# SCH_MedySync_2024-07-15.net
KiCad netlist of a schematic drawn in EasyEDA
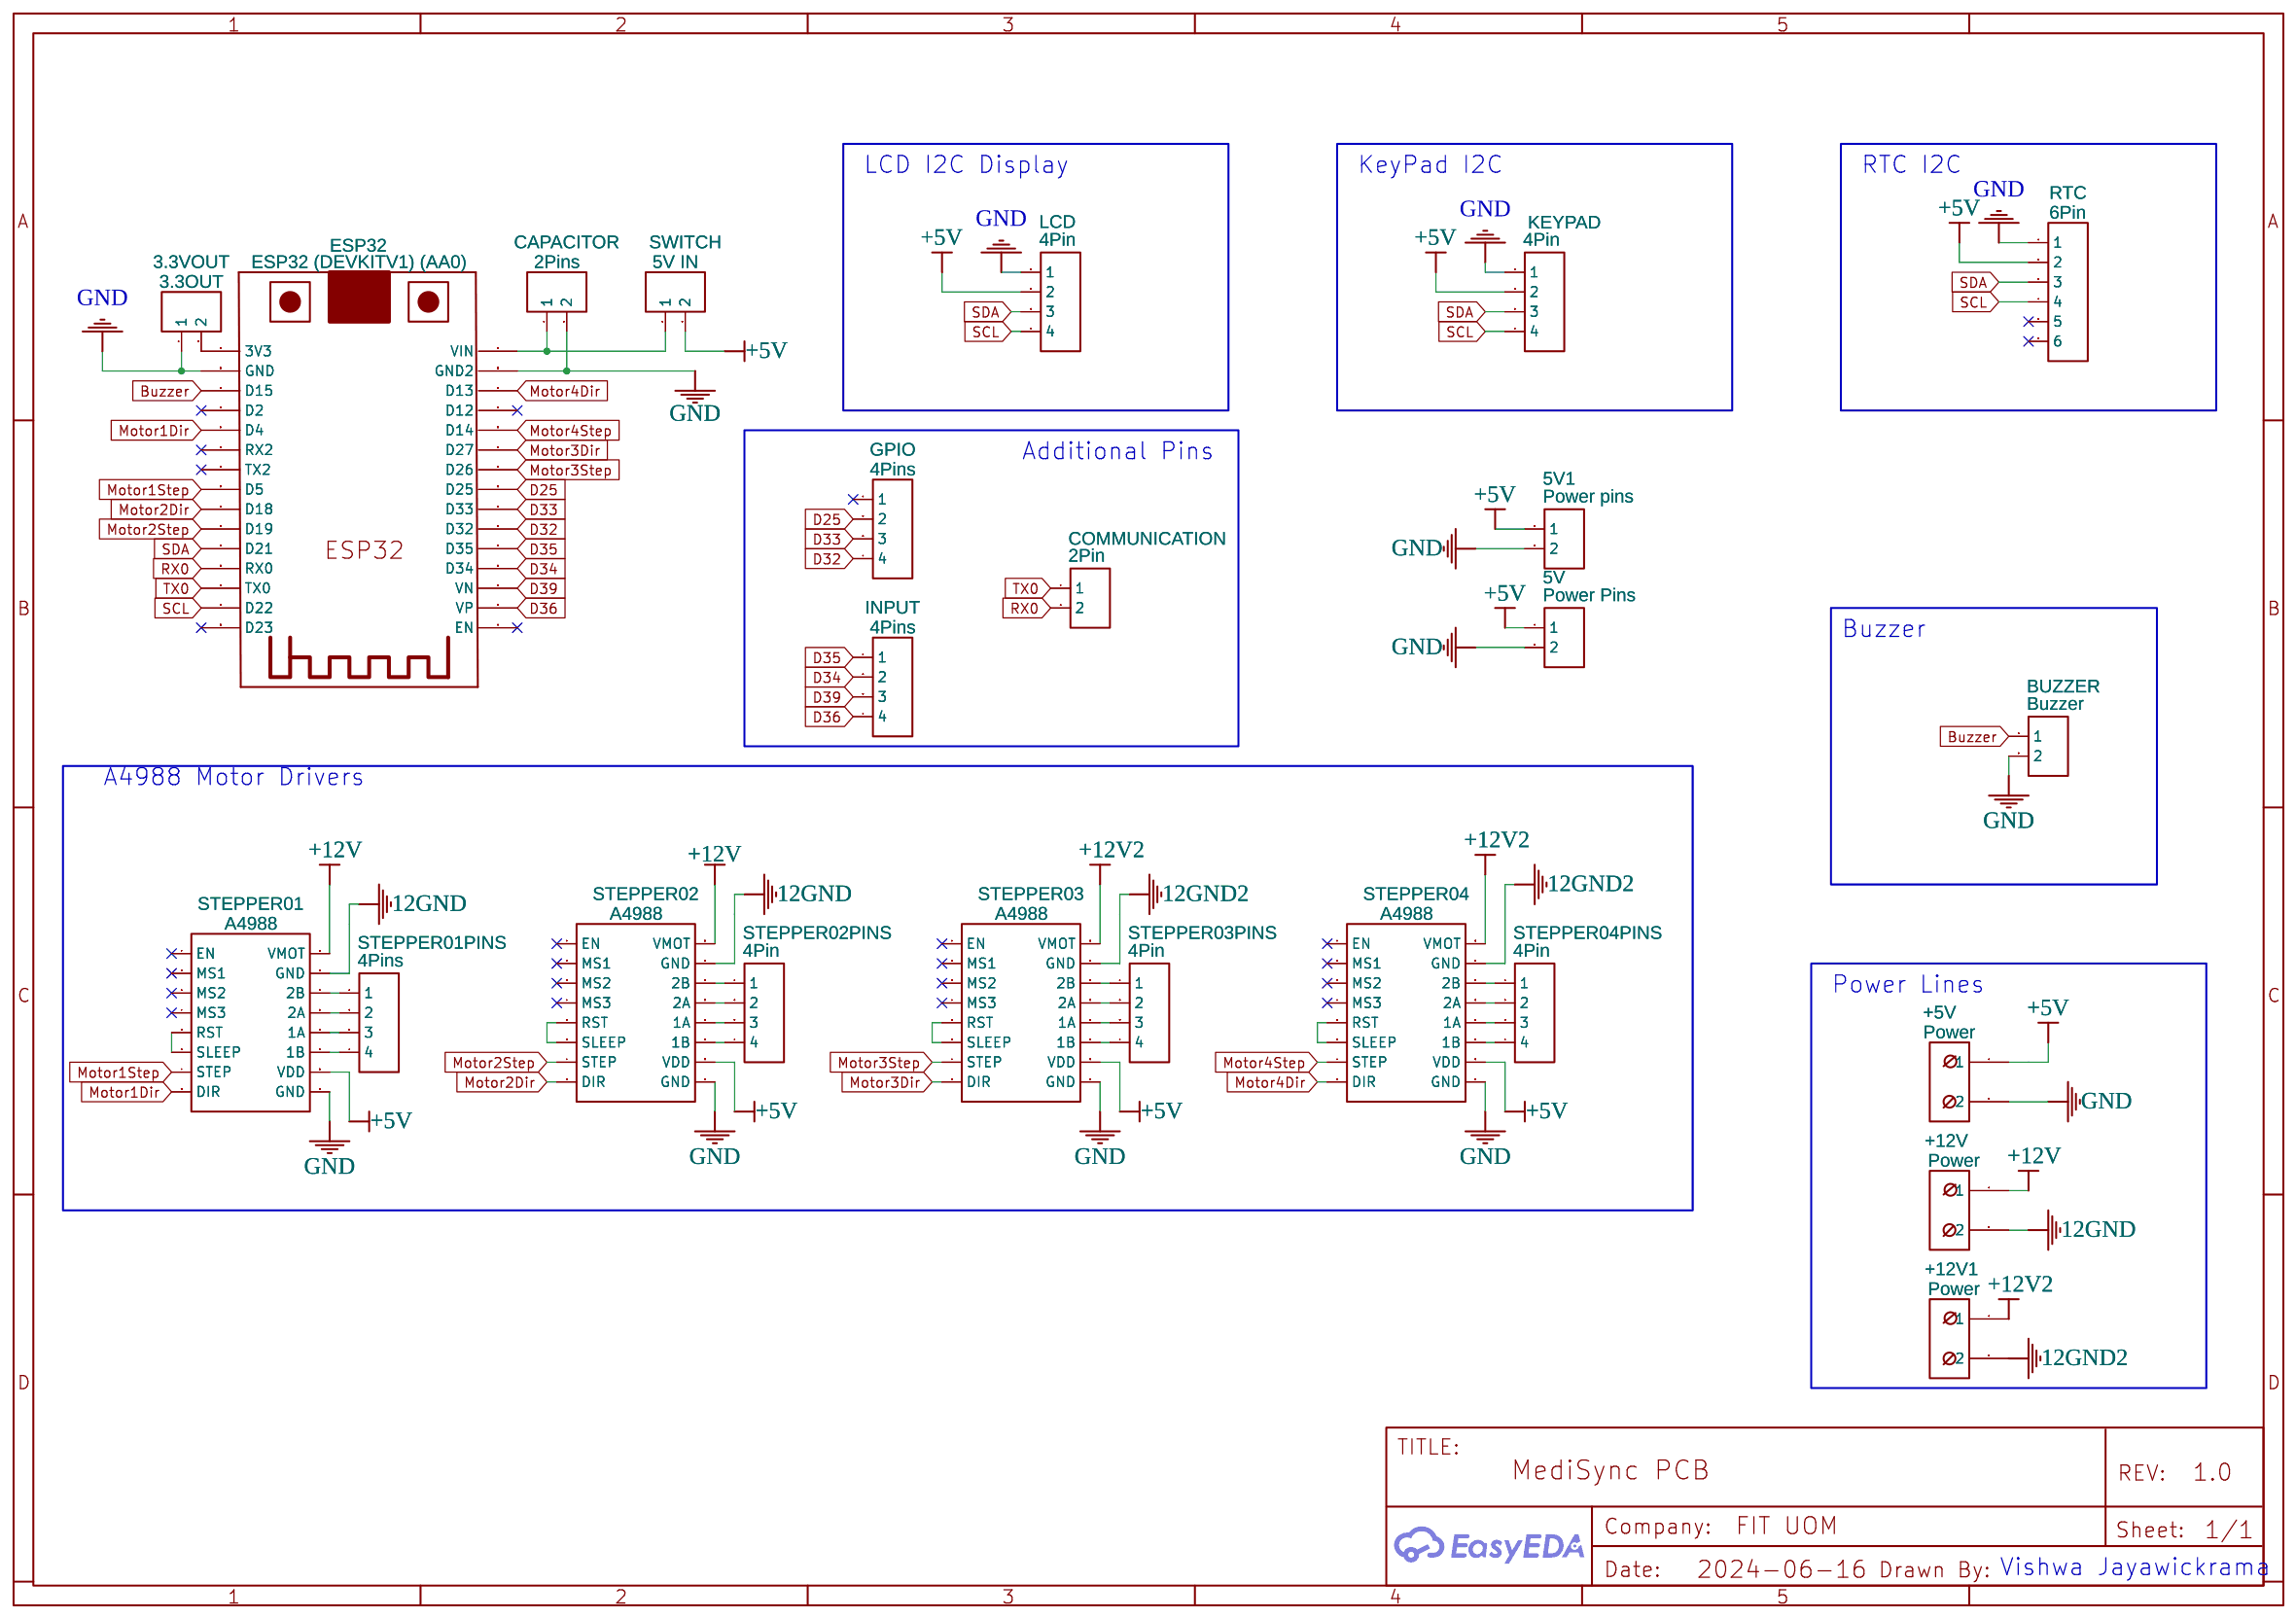
[diagram p0: schematic sheet]

(export (version "E")
  (design (tool "Eeschema 10.0.6"))
  (components
    (comp (ref "+5V") (value "Power") (libsource (lib "") (part "2POSITION_TERMINAL_BLOCK_1")))
    (comp (ref "+12V") (value "Power") (libsource (lib "") (part "2POSITION_TERMINAL_BLOCK")))
    (comp (ref "+12V1") (value "Power") (libsource (lib "") (part "2POSITION_TERMINAL_BLOCK")))
    (comp (ref "3.3VOUT") (value "3.3OUT") (libsource (lib "") (part "HDR-M-2.54_1x2_3")))
    (comp (ref "5V") (value "Power Pins") (libsource (lib "") (part "HDR-M-2.54_1x2")))
    (comp (ref "5V1") (value "Power pins") (libsource (lib "") (part "HDR-M-2.54_1x2")))
    (comp (ref "BUZZER") (value "Buzzer") (libsource (lib "") (part "HDR-M-2.54_1x2_2")))
    (comp (ref "CAPACITOR") (value "2Pins") (libsource (lib "") (part "HDR-F-2.54_1x2")))
    (comp (ref "COMMUNICATION") (value "2Pin") (libsource (lib "") (part "HDR-M-2.54_1x2_1")))
    (comp (ref "ESP32") (value "ESP32 (DEVKITV1) (AA0)") (libsource (lib "") (part "ESP32-DEVKIT-V1-30PIN")))
    (comp (ref "GPIO") (value "4Pins") (libsource (lib "") (part "HDR-M-2.54_1x4_3")))
    (comp (ref "INPUT") (value "4Pins") (libsource (lib "") (part "HDR-M-2.54_1x4_2")))
    (comp (ref "KEYPAD") (value "4Pin") (libsource (lib "") (part "HDR-M-2.54_1x4_6")))
    (comp (ref "LCD") (value "4Pin") (libsource (lib "") (part "HDR-M-2.54_1x4_7")))
    (comp (ref "RTC") (value "6Pin") (libsource (lib "") (part "HDR-F-2.54_1x6")))
    (comp (ref "STEPPER01") (value "A4988") (libsource (lib "") (part "A4988")))
    (comp (ref "STEPPER01PINS") (value "4Pins") (libsource (lib "") (part "HDR-M-2.54_1x4_4")))
    (comp (ref "STEPPER02") (value "A4988") (libsource (lib "") (part "A4988")))
    (comp (ref "STEPPER02PINS") (value "4Pin") (libsource (lib "") (part "HDR-M-2.54_1x4")))
    (comp (ref "STEPPER03") (value "A4988") (libsource (lib "") (part "A4988")))
    (comp (ref "STEPPER03PINS") (value "4Pin") (libsource (lib "") (part "HDR-M-2.54_1x4_1")))
    (comp (ref "STEPPER04") (value "A4988") (libsource (lib "") (part "A4988")))
    (comp (ref "STEPPER04PINS") (value "4Pin") (libsource (lib "") (part "HDR-M-2.54_1x4_5")))
    (comp (ref "SWITCH") (value "5V IN") (libsource (lib "") (part "HDR-M-2.54_1x2_4")))
  )
  (nets
    (net (code "1") (name "+5V") (class "Default")
      (node (ref "+5V") (pin "1") (pinfunction "1_1") (pintype "unspecified"))
      (node (ref "5V") (pin "1") (pinfunction "1_1") (pintype "unspecified"))
      (node (ref "5V1") (pin "1") (pinfunction "1_1") (pintype "unspecified"))
      (node (ref "KEYPAD") (pin "2") (pinfunction "2_2") (pintype "unspecified"))
      (node (ref "LCD") (pin "2") (pinfunction "2_2") (pintype "unspecified"))
      (node (ref "RTC") (pin "2") (pinfunction "2_2") (pintype "input"))
      (node (ref "STEPPER01") (pin "15") (pinfunction "VDD_15") (pintype "unspecified"))
      (node (ref "STEPPER02") (pin "15") (pinfunction "VDD_15") (pintype "unspecified"))
      (node (ref "STEPPER03") (pin "15") (pinfunction "VDD_15") (pintype "unspecified"))
      (node (ref "STEPPER04") (pin "15") (pinfunction "VDD_15") (pintype "unspecified"))
      (node (ref "SWITCH") (pin "2") (pinfunction "2_2") (pintype "unspecified"))
    )
    (net (code "2") (name "+12V") (class "Default")
      (node (ref "+12V") (pin "1") (pinfunction "1_1") (pintype "unspecified"))
      (node (ref "STEPPER01") (pin "9") (pinfunction "VMOT_9") (pintype "unspecified"))
      (node (ref "STEPPER02") (pin "9") (pinfunction "VMOT_9") (pintype "unspecified"))
    )
    (net (code "3") (name "+12V2") (class "Default")
      (node (ref "+12V1") (pin "1") (pinfunction "1_1") (pintype "unspecified"))
      (node (ref "STEPPER03") (pin "9") (pinfunction "VMOT_9") (pintype "unspecified"))
      (node (ref "STEPPER04") (pin "9") (pinfunction "VMOT_9") (pintype "unspecified"))
    )
    (net (code "4") (name "12GND") (class "Default")
      (node (ref "+12V") (pin "2") (pinfunction "2_2") (pintype "unspecified"))
      (node (ref "STEPPER01") (pin "10") (pinfunction "GND_10") (pintype "unspecified"))
      (node (ref "STEPPER02") (pin "10") (pinfunction "GND_10") (pintype "unspecified"))
    )
    (net (code "5") (name "12GND2") (class "Default")
      (node (ref "+12V1") (pin "2") (pinfunction "2_2") (pintype "unspecified"))
      (node (ref "STEPPER03") (pin "10") (pinfunction "GND_10") (pintype "unspecified"))
      (node (ref "STEPPER04") (pin "10") (pinfunction "GND_10") (pintype "unspecified"))
    )
    (net (code "6") (name "Buzzer") (class "Default")
      (node (ref "BUZZER") (pin "1") (pinfunction "1_1") (pintype "unspecified"))
      (node (ref "ESP32") (pin "D15") (pinfunction "D15_D15") (pintype "unspecified"))
    )
    (net (code "7") (name "D25") (class "Default")
      (node (ref "ESP32") (pin "D25") (pinfunction "D25_D25") (pintype "unspecified"))
      (node (ref "GPIO") (pin "2") (pinfunction "2_2") (pintype "unspecified"))
    )
    (net (code "8") (name "D32") (class "Default")
      (node (ref "ESP32") (pin "D32") (pinfunction "D32_D32") (pintype "unspecified"))
      (node (ref "GPIO") (pin "4") (pinfunction "4_4") (pintype "unspecified"))
    )
    (net (code "9") (name "D33") (class "Default")
      (node (ref "ESP32") (pin "D33") (pinfunction "D33_D33") (pintype "unspecified"))
      (node (ref "GPIO") (pin "3") (pinfunction "3_3") (pintype "unspecified"))
    )
    (net (code "10") (name "D34") (class "Default")
      (node (ref "ESP32") (pin "D34") (pinfunction "D34_D34") (pintype "unspecified"))
      (node (ref "INPUT") (pin "2") (pinfunction "2_2") (pintype "unspecified"))
    )
    (net (code "11") (name "D35") (class "Default")
      (node (ref "ESP32") (pin "D35") (pinfunction "D35_D35") (pintype "unspecified"))
      (node (ref "INPUT") (pin "1") (pinfunction "1_1") (pintype "unspecified"))
    )
    (net (code "12") (name "D36") (class "Default")
      (node (ref "ESP32") (pin "VP") (pinfunction "VP_VP") (pintype "unspecified"))
      (node (ref "INPUT") (pin "4") (pinfunction "4_4") (pintype "unspecified"))
    )
    (net (code "13") (name "D39") (class "Default")
      (node (ref "ESP32") (pin "VN") (pinfunction "VN_VN") (pintype "unspecified"))
      (node (ref "INPUT") (pin "3") (pinfunction "3_3") (pintype "unspecified"))
    )
    (net (code "14") (name "GND") (class "Default")
      (node (ref "+5V") (pin "2") (pinfunction "2_2") (pintype "unspecified"))
      (node (ref "3.3VOUT") (pin "1") (pinfunction "1_1") (pintype "unspecified"))
      (node (ref "5V") (pin "2") (pinfunction "2_2") (pintype "unspecified"))
      (node (ref "5V1") (pin "2") (pinfunction "2_2") (pintype "unspecified"))
      (node (ref "BUZZER") (pin "2") (pinfunction "2_2") (pintype "unspecified"))
      (node (ref "CAPACITOR") (pin "2") (pinfunction "2_2") (pintype "input"))
      (node (ref "ESP32") (pin "GND") (pinfunction "GND_GND") (pintype "unspecified"))
      (node (ref "ESP32") (pin "GND2") (pinfunction "GND2_GND2") (pintype "unspecified"))
      (node (ref "KEYPAD") (pin "1") (pinfunction "1_1") (pintype "unspecified"))
      (node (ref "LCD") (pin "1") (pinfunction "1_1") (pintype "unspecified"))
      (node (ref "RTC") (pin "1") (pinfunction "1_1") (pintype "input"))
      (node (ref "STEPPER01") (pin "16") (pinfunction "GND_16") (pintype "unspecified"))
      (node (ref "STEPPER02") (pin "16") (pinfunction "GND_16") (pintype "unspecified"))
      (node (ref "STEPPER03") (pin "16") (pinfunction "GND_16") (pintype "unspecified"))
      (node (ref "STEPPER04") (pin "16") (pinfunction "GND_16") (pintype "unspecified"))
    )
    (net (code "15") (name "Motor1Dir") (class "Default")
      (node (ref "ESP32") (pin "D4") (pinfunction "D4_D4") (pintype "unspecified"))
      (node (ref "STEPPER01") (pin "8") (pinfunction "DIR_8") (pintype "unspecified"))
    )
    (net (code "16") (name "Motor1Step") (class "Default")
      (node (ref "ESP32") (pin "D5") (pinfunction "D5_D5") (pintype "unspecified"))
      (node (ref "STEPPER01") (pin "7") (pinfunction "STEP_7") (pintype "unspecified"))
    )
    (net (code "17") (name "Motor2Dir") (class "Default")
      (node (ref "ESP32") (pin "D18") (pinfunction "D18_D18") (pintype "unspecified"))
      (node (ref "STEPPER02") (pin "8") (pinfunction "DIR_8") (pintype "unspecified"))
    )
    (net (code "18") (name "Motor2Step") (class "Default")
      (node (ref "ESP32") (pin "D19") (pinfunction "D19_D19") (pintype "unspecified"))
      (node (ref "STEPPER02") (pin "7") (pinfunction "STEP_7") (pintype "unspecified"))
    )
    (net (code "19") (name "Motor3Dir") (class "Default")
      (node (ref "ESP32") (pin "D27") (pinfunction "D27_D27") (pintype "unspecified"))
      (node (ref "STEPPER03") (pin "8") (pinfunction "DIR_8") (pintype "unspecified"))
    )
    (net (code "20") (name "Motor3Step") (class "Default")
      (node (ref "ESP32") (pin "D26") (pinfunction "D26_D26") (pintype "unspecified"))
      (node (ref "STEPPER03") (pin "7") (pinfunction "STEP_7") (pintype "unspecified"))
    )
    (net (code "21") (name "Motor4Dir") (class "Default")
      (node (ref "ESP32") (pin "D13") (pinfunction "D13_D13") (pintype "unspecified"))
      (node (ref "STEPPER04") (pin "8") (pinfunction "DIR_8") (pintype "unspecified"))
    )
    (net (code "22") (name "Motor4Step") (class "Default")
      (node (ref "ESP32") (pin "D14") (pinfunction "D14_D14") (pintype "unspecified"))
      (node (ref "STEPPER04") (pin "7") (pinfunction "STEP_7") (pintype "unspecified"))
    )
    (net (code "23") (name "Net-(3.3VOUT-Pad2)") (class "Default")
      (node (ref "3.3VOUT") (pin "2") (pinfunction "2_2") (pintype "unspecified"))
      (node (ref "ESP32") (pin "3V3") (pinfunction "3V3_3V3") (pintype "unspecified"))
    )
    (net (code "24") (name "Net-(CAPACITOR-Pad1)") (class "Default")
      (node (ref "CAPACITOR") (pin "1") (pinfunction "1_1") (pintype "input"))
      (node (ref "ESP32") (pin "VIN") (pinfunction "VIN_VIN") (pintype "unspecified"))
      (node (ref "SWITCH") (pin "1") (pinfunction "1_1") (pintype "unspecified"))
    )
    (net (code "25") (name "Net-(STEPPER01-1A)") (class "Default")
      (node (ref "STEPPER01") (pin "13") (pinfunction "1A_13") (pintype "unspecified"))
      (node (ref "STEPPER01PINS") (pin "3") (pinfunction "3_3") (pintype "unspecified"))
    )
    (net (code "26") (name "Net-(STEPPER01-1B)") (class "Default")
      (node (ref "STEPPER01") (pin "14") (pinfunction "1B_14") (pintype "unspecified"))
      (node (ref "STEPPER01PINS") (pin "4") (pinfunction "4_4") (pintype "unspecified"))
    )
    (net (code "27") (name "Net-(STEPPER01-2A)") (class "Default")
      (node (ref "STEPPER01") (pin "12") (pinfunction "2A_12") (pintype "unspecified"))
      (node (ref "STEPPER01PINS") (pin "2") (pinfunction "2_2") (pintype "unspecified"))
    )
    (net (code "28") (name "Net-(STEPPER01-2B)") (class "Default")
      (node (ref "STEPPER01") (pin "11") (pinfunction "2B_11") (pintype "unspecified"))
      (node (ref "STEPPER01PINS") (pin "1") (pinfunction "1_1") (pintype "unspecified"))
    )
    (net (code "29") (name "Net-(STEPPER01-RST)") (class "Default")
      (node (ref "STEPPER01") (pin "5") (pinfunction "RST_5") (pintype "unspecified"))
      (node (ref "STEPPER01") (pin "6") (pinfunction "SLEEP_6") (pintype "unspecified"))
    )
    (net (code "30") (name "Net-(STEPPER02-1A)") (class "Default")
      (node (ref "STEPPER02") (pin "13") (pinfunction "1A_13") (pintype "unspecified"))
      (node (ref "STEPPER02PINS") (pin "3") (pinfunction "3_3") (pintype "unspecified"))
    )
    (net (code "31") (name "Net-(STEPPER02-1B)") (class "Default")
      (node (ref "STEPPER02") (pin "14") (pinfunction "1B_14") (pintype "unspecified"))
      (node (ref "STEPPER02PINS") (pin "4") (pinfunction "4_4") (pintype "unspecified"))
    )
    (net (code "32") (name "Net-(STEPPER02-2A)") (class "Default")
      (node (ref "STEPPER02") (pin "12") (pinfunction "2A_12") (pintype "unspecified"))
      (node (ref "STEPPER02PINS") (pin "2") (pinfunction "2_2") (pintype "unspecified"))
    )
    (net (code "33") (name "Net-(STEPPER02-2B)") (class "Default")
      (node (ref "STEPPER02") (pin "11") (pinfunction "2B_11") (pintype "unspecified"))
      (node (ref "STEPPER02PINS") (pin "1") (pinfunction "1_1") (pintype "unspecified"))
    )
    (net (code "34") (name "Net-(STEPPER02-RST)") (class "Default")
      (node (ref "STEPPER02") (pin "5") (pinfunction "RST_5") (pintype "unspecified"))
      (node (ref "STEPPER02") (pin "6") (pinfunction "SLEEP_6") (pintype "unspecified"))
    )
    (net (code "35") (name "Net-(STEPPER03-1A)") (class "Default")
      (node (ref "STEPPER03") (pin "13") (pinfunction "1A_13") (pintype "unspecified"))
      (node (ref "STEPPER03PINS") (pin "3") (pinfunction "3_3") (pintype "unspecified"))
    )
    (net (code "36") (name "Net-(STEPPER03-1B)") (class "Default")
      (node (ref "STEPPER03") (pin "14") (pinfunction "1B_14") (pintype "unspecified"))
      (node (ref "STEPPER03PINS") (pin "4") (pinfunction "4_4") (pintype "unspecified"))
    )
    (net (code "37") (name "Net-(STEPPER03-2A)") (class "Default")
      (node (ref "STEPPER03") (pin "12") (pinfunction "2A_12") (pintype "unspecified"))
      (node (ref "STEPPER03PINS") (pin "2") (pinfunction "2_2") (pintype "unspecified"))
    )
    (net (code "38") (name "Net-(STEPPER03-2B)") (class "Default")
      (node (ref "STEPPER03") (pin "11") (pinfunction "2B_11") (pintype "unspecified"))
      (node (ref "STEPPER03PINS") (pin "1") (pinfunction "1_1") (pintype "unspecified"))
    )
    (net (code "39") (name "Net-(STEPPER03-RST)") (class "Default")
      (node (ref "STEPPER03") (pin "5") (pinfunction "RST_5") (pintype "unspecified"))
      (node (ref "STEPPER03") (pin "6") (pinfunction "SLEEP_6") (pintype "unspecified"))
    )
    (net (code "40") (name "Net-(STEPPER04-1A)") (class "Default")
      (node (ref "STEPPER04") (pin "13") (pinfunction "1A_13") (pintype "unspecified"))
      (node (ref "STEPPER04PINS") (pin "3") (pinfunction "3_3") (pintype "unspecified"))
    )
    (net (code "41") (name "Net-(STEPPER04-1B)") (class "Default")
      (node (ref "STEPPER04") (pin "14") (pinfunction "1B_14") (pintype "unspecified"))
      (node (ref "STEPPER04PINS") (pin "4") (pinfunction "4_4") (pintype "unspecified"))
    )
    (net (code "42") (name "Net-(STEPPER04-2A)") (class "Default")
      (node (ref "STEPPER04") (pin "12") (pinfunction "2A_12") (pintype "unspecified"))
      (node (ref "STEPPER04PINS") (pin "2") (pinfunction "2_2") (pintype "unspecified"))
    )
    (net (code "43") (name "Net-(STEPPER04-2B)") (class "Default")
      (node (ref "STEPPER04") (pin "11") (pinfunction "2B_11") (pintype "unspecified"))
      (node (ref "STEPPER04PINS") (pin "1") (pinfunction "1_1") (pintype "unspecified"))
    )
    (net (code "44") (name "Net-(STEPPER04-RST)") (class "Default")
      (node (ref "STEPPER04") (pin "5") (pinfunction "RST_5") (pintype "unspecified"))
      (node (ref "STEPPER04") (pin "6") (pinfunction "SLEEP_6") (pintype "unspecified"))
    )
    (net (code "45") (name "RX0") (class "Default")
      (node (ref "COMMUNICATION") (pin "2") (pinfunction "2_2") (pintype "unspecified"))
      (node (ref "ESP32") (pin "RX0") (pinfunction "RX0_RX0") (pintype "unspecified"))
    )
    (net (code "46") (name "SCL") (class "Default")
      (node (ref "ESP32") (pin "D22") (pinfunction "D22_D22") (pintype "unspecified"))
      (node (ref "KEYPAD") (pin "4") (pinfunction "4_4") (pintype "unspecified"))
      (node (ref "LCD") (pin "4") (pinfunction "4_4") (pintype "unspecified"))
      (node (ref "RTC") (pin "4") (pinfunction "4_4") (pintype "input"))
    )
    (net (code "47") (name "SDA") (class "Default")
      (node (ref "ESP32") (pin "D21") (pinfunction "D21_D21") (pintype "unspecified"))
      (node (ref "KEYPAD") (pin "3") (pinfunction "3_3") (pintype "unspecified"))
      (node (ref "LCD") (pin "3") (pinfunction "3_3") (pintype "unspecified"))
      (node (ref "RTC") (pin "3") (pinfunction "3_3") (pintype "input"))
    )
    (net (code "48") (name "TX0") (class "Default")
      (node (ref "COMMUNICATION") (pin "1") (pinfunction "1_1") (pintype "unspecified"))
      (node (ref "ESP32") (pin "TX0") (pinfunction "TX0_TX0") (pintype "unspecified"))
    )
    (net (code "49") (name "unconnected-(ESP32-PadD2)") (class "Default")
      (node (ref "ESP32") (pin "D2") (pinfunction "D2_D2") (pintype "unspecified+no_connect"))
    )
    (net (code "50") (name "unconnected-(ESP32-PadD12)") (class "Default")
      (node (ref "ESP32") (pin "D12") (pinfunction "D12_D12") (pintype "unspecified+no_connect"))
    )
    (net (code "51") (name "unconnected-(ESP32-PadD23)") (class "Default")
      (node (ref "ESP32") (pin "D23") (pinfunction "D23_D23") (pintype "unspecified+no_connect"))
    )
    (net (code "52") (name "unconnected-(ESP32-PadEN)") (class "Default")
      (node (ref "ESP32") (pin "EN") (pinfunction "EN_EN") (pintype "unspecified+no_connect"))
    )
    (net (code "53") (name "unconnected-(ESP32-PadRX2)") (class "Default")
      (node (ref "ESP32") (pin "RX2") (pinfunction "RX2_RX2") (pintype "unspecified+no_connect"))
    )
    (net (code "54") (name "unconnected-(ESP32-PadTX2)") (class "Default")
      (node (ref "ESP32") (pin "TX2") (pinfunction "TX2_TX2") (pintype "unspecified+no_connect"))
    )
    (net (code "55") (name "unconnected-(GPIO-Pad1)") (class "Default")
      (node (ref "GPIO") (pin "1") (pinfunction "1_1") (pintype "unspecified+no_connect"))
    )
    (net (code "56") (name "unconnected-(RTC-Pad5)") (class "Default")
      (node (ref "RTC") (pin "5") (pinfunction "5_5") (pintype "input+no_connect"))
    )
    (net (code "57") (name "unconnected-(RTC-Pad6)") (class "Default")
      (node (ref "RTC") (pin "6") (pinfunction "6_6") (pintype "input+no_connect"))
    )
    (net (code "58") (name "unconnected-(STEPPER01-EN-Pad1)") (class "Default")
      (node (ref "STEPPER01") (pin "1") (pinfunction "EN_1") (pintype "unspecified+no_connect"))
    )
    (net (code "59") (name "unconnected-(STEPPER01-MS1-Pad2)") (class "Default")
      (node (ref "STEPPER01") (pin "2") (pinfunction "MS1_2") (pintype "unspecified+no_connect"))
    )
    (net (code "60") (name "unconnected-(STEPPER01-MS2-Pad3)") (class "Default")
      (node (ref "STEPPER01") (pin "3") (pinfunction "MS2_3") (pintype "unspecified+no_connect"))
    )
    (net (code "61") (name "unconnected-(STEPPER01-MS3-Pad4)") (class "Default")
      (node (ref "STEPPER01") (pin "4") (pinfunction "MS3_4") (pintype "unspecified+no_connect"))
    )
    (net (code "62") (name "unconnected-(STEPPER02-EN-Pad1)") (class "Default")
      (node (ref "STEPPER02") (pin "1") (pinfunction "EN_1") (pintype "unspecified+no_connect"))
    )
    (net (code "63") (name "unconnected-(STEPPER02-MS1-Pad2)") (class "Default")
      (node (ref "STEPPER02") (pin "2") (pinfunction "MS1_2") (pintype "unspecified+no_connect"))
    )
    (net (code "64") (name "unconnected-(STEPPER02-MS2-Pad3)") (class "Default")
      (node (ref "STEPPER02") (pin "3") (pinfunction "MS2_3") (pintype "unspecified+no_connect"))
    )
    (net (code "65") (name "unconnected-(STEPPER02-MS3-Pad4)") (class "Default")
      (node (ref "STEPPER02") (pin "4") (pinfunction "MS3_4") (pintype "unspecified+no_connect"))
    )
    (net (code "66") (name "unconnected-(STEPPER03-EN-Pad1)") (class "Default")
      (node (ref "STEPPER03") (pin "1") (pinfunction "EN_1") (pintype "unspecified+no_connect"))
    )
    (net (code "67") (name "unconnected-(STEPPER03-MS1-Pad2)") (class "Default")
      (node (ref "STEPPER03") (pin "2") (pinfunction "MS1_2") (pintype "unspecified+no_connect"))
    )
    (net (code "68") (name "unconnected-(STEPPER03-MS2-Pad3)") (class "Default")
      (node (ref "STEPPER03") (pin "3") (pinfunction "MS2_3") (pintype "unspecified+no_connect"))
    )
    (net (code "69") (name "unconnected-(STEPPER03-MS3-Pad4)") (class "Default")
      (node (ref "STEPPER03") (pin "4") (pinfunction "MS3_4") (pintype "unspecified+no_connect"))
    )
    (net (code "70") (name "unconnected-(STEPPER04-EN-Pad1)") (class "Default")
      (node (ref "STEPPER04") (pin "1") (pinfunction "EN_1") (pintype "unspecified+no_connect"))
    )
    (net (code "71") (name "unconnected-(STEPPER04-MS1-Pad2)") (class "Default")
      (node (ref "STEPPER04") (pin "2") (pinfunction "MS1_2") (pintype "unspecified+no_connect"))
    )
    (net (code "72") (name "unconnected-(STEPPER04-MS2-Pad3)") (class "Default")
      (node (ref "STEPPER04") (pin "3") (pinfunction "MS2_3") (pintype "unspecified+no_connect"))
    )
    (net (code "73") (name "unconnected-(STEPPER04-MS3-Pad4)") (class "Default")
      (node (ref "STEPPER04") (pin "4") (pinfunction "MS3_4") (pintype "unspecified+no_connect"))
    )
  )
)
